# Temperature_sensing_and_heater_power.net
KiCad netlist of a schematic drawn in Altium Designer
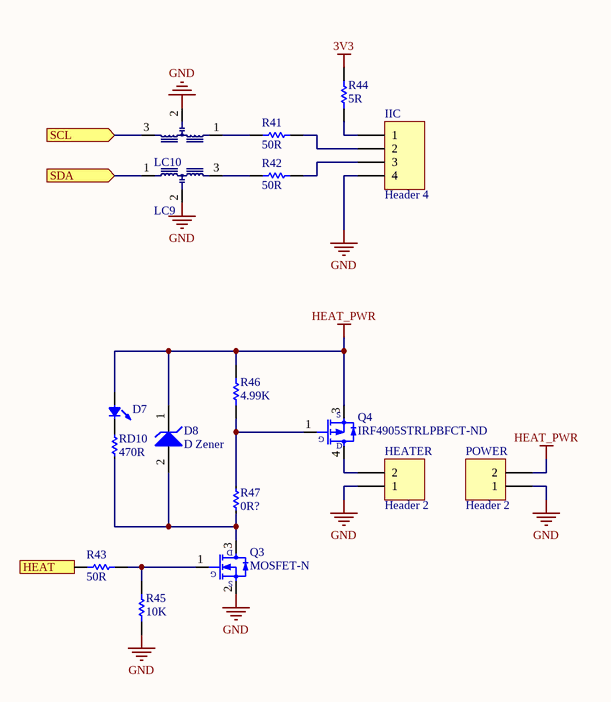
[diagram p0: Temperature sensing and heater power.SchDoc]

(export (version "E")
  (design (tool "Eeschema 10.0.6"))
  (components
    (comp (ref "D7")
      (value "LED0")
      (footprint "T1 LED")
      (description "T 1 3/4 LED")
      (fields (field (name "PUBLISHER") "Altium Limited"))
      (libsource (lib "Miscellaneous Devices") (part "LED0"))
    )
    (comp (ref "D8")
      (value "D Zener")
      (footprint "SOD123/X.85")
      (description "Zener Diode")
      (fields (field (name "PUBLISHER") "Altium Limited"))
      (libsource (lib "Miscellaneous Devices") (part "D Zener"))
    )
    (comp (ref "HEATER")
      (value "Header 2")
      (footprint "Molex Mini-Fit Jr 5569 - 2 Pin, RA")
      (description "Header, 2-Pin")
      (fields (field (name "PUBLISHER") "Altium Limited"))
      (libsource (lib "") (part "Header 2_1"))
    )
    (comp (ref "IIC")
      (value "Header 4")
      (footprint "AMPModu MTE 4 Pin Shrouded Header")
      (description "Header, 4-Pin")
      (fields (field (name "PUBLISHER") "Altium Limited"))
      (libsource (lib "Miscellaneous Connectors") (part "Header 4"))
    )
    (comp (ref "LC9")
      (value "MEM2012F")
      (footprint "MEM2012S LC Filter")
      (description "Signal Line 3-terminal Filters")
      (libsource (lib "Unsorted") (part "MEM2012F - Signal Filter"))
    )
    (comp (ref "LC10")
      (value "MEM2012F")
      (footprint "MEM2012S LC Filter")
      (description "Signal Line 3-terminal Filters")
      (libsource (lib "Unsorted") (part "MEM2012F - Signal Filter"))
    )
    (comp (ref "POWER")
      (value "Header 2")
      (footprint "Molex Mini-Fit Jr 5569 - 2 Pin, RA")
      (description "Header, 2-Pin")
      (fields (field (name "PUBLISHER") "Altium Limited"))
      (libsource (lib "Miscellaneous Connectors") (part "Header 2"))
    )
    (comp (ref "Q3")
      (value "MOSFET-N")
      (footprint "SOT23-3N")
      (description "N-Channel MOSFET")
      (fields (field (name "PUBLISHER") "Altium Limited"))
      (libsource (lib "Miscellaneous Devices") (part "MOSFET-N"))
    )
    (comp (ref "Q4")
      (value "IRF4905STRLPBFCT-ND")
      (footprint "TO254P1520-3_4N")
      (description "P-Channel MOSFET")
      (fields (field (name "PUBLISHER") "Altium Limited"))
      (libsource (lib "Miscellaneous Devices") (part "MOSFET-P"))
    )
    (comp (ref "R41")
      (value "50R")
      (footprint "0603R")
      (description "Semiconductor Resistor")
      (fields (field (name "Comment") "Res Semi") (field (name "PUBLISHER") "Altium Limited"))
      (libsource (lib "Miscellaneous Devices") (part "Res Semi"))
    )
    (comp (ref "R42")
      (value "50R")
      (footprint "0603R")
      (description "Semiconductor Resistor")
      (fields (field (name "Comment") "Res Semi") (field (name "PUBLISHER") "Altium Limited"))
      (libsource (lib "Miscellaneous Devices") (part "Res Semi"))
    )
    (comp (ref "R43")
      (value "50R")
      (footprint "0603R")
      (description "Semiconductor Resistor")
      (fields (field (name "Comment") "Res Semi") (field (name "PUBLISHER") "Altium Limited"))
      (libsource (lib "Miscellaneous Devices") (part "Res Semi"))
    )
    (comp (ref "R44")
      (value "5R")
      (footprint "1206R")
      (description "Semiconductor Resistor")
      (fields (field (name "Comment") "Res Semi") (field (name "PUBLISHER") "Altium Limited"))
      (libsource (lib "Miscellaneous Devices") (part "Res Semi"))
    )
    (comp (ref "R45")
      (value "10K")
      (footprint "0603R")
      (description "Semiconductor Resistor")
      (fields (field (name "Comment") "Res Semi") (field (name "PUBLISHER") "Altium Limited"))
      (libsource (lib "Miscellaneous Devices") (part "Res Semi"))
    )
    (comp (ref "R46")
      (value "4.99K")
      (footprint "1206R")
      (description "Semiconductor Resistor")
      (fields (field (name "Comment") "Res Semi") (field (name "PUBLISHER") "Altium Limited"))
      (libsource (lib "Miscellaneous Devices") (part "Res Semi"))
    )
    (comp (ref "R47")
      (value "0R?")
      (footprint "0603R")
      (description "Semiconductor Resistor")
      (fields (field (name "Comment") "Res Semi Small") (field (name "PUBLISHER") "Altium Limited"))
      (libsource (lib "Miscellaneous Devices") (part "Res Semi Small"))
    )
    (comp (ref "RD10")
      (value "470R")
      (footprint "0603R")
      (description "Semiconductor Resistor")
      (fields (field (name "Comment") "Res Semi Small") (field (name "PUBLISHER") "Altium Limited"))
      (libsource (lib "Miscellaneous Devices") (part "Res Semi Small"))
    )
  )
  (nets
    (net (code "1") (name "/HEAT") (class "Default")
      (node (ref "R43") (pin "1") (pinfunction "1_1") (pintype "passive"))
    )
    (net (code "2") (name "/SCL") (class "Default")
      (node (ref "LC10") (pin "3") (pinfunction "3_3") (pintype "passive"))
    )
    (net (code "3") (name "/SDA") (class "Default")
      (node (ref "LC9") (pin "1") (pinfunction "1_1") (pintype "passive"))
    )
    (net (code "4") (name "3V3") (class "Default")
      (node (ref "R44") (pin "2") (pinfunction "2_2") (pintype "passive"))
    )
    (net (code "5") (name "GND") (class "Default")
      (node (ref "HEATER") (pin "1") (pinfunction "1_1") (pintype "passive"))
      (node (ref "IIC") (pin "4") (pinfunction "4_4") (pintype "passive"))
      (node (ref "LC10") (pin "2") (pinfunction "2_2") (pintype "passive"))
      (node (ref "LC9") (pin "2") (pinfunction "2_2") (pintype "passive"))
      (node (ref "POWER") (pin "1") (pinfunction "1_1") (pintype "passive"))
      (node (ref "Q3") (pin "2") (pinfunction "S_2") (pintype "passive"))
      (node (ref "R45") (pin "1") (pinfunction "1_1") (pintype "passive"))
    )
    (net (code "6") (name "HEAT_PWR") (class "Default")
      (node (ref "D7") (pin "1") (pinfunction "1_1") (pintype "passive"))
      (node (ref "D8") (pin "1") (pinfunction "A_1") (pintype "passive"))
      (node (ref "POWER") (pin "2") (pinfunction "2_2") (pintype "passive"))
      (node (ref "Q4") (pin "3") (pinfunction "D_3") (pintype "passive"))
      (node (ref "R46") (pin "2") (pinfunction "2_2") (pintype "passive"))
    )
    (net (code "7") (name "Net-(D7-Pad2)") (class "Default")
      (node (ref "D7") (pin "2") (pinfunction "2_2") (pintype "passive"))
      (node (ref "RD10") (pin "1") (pinfunction "1_1") (pintype "passive"))
    )
    (net (code "8") (name "Net-(D8-K)") (class "Default")
      (node (ref "D8") (pin "2") (pinfunction "K_2") (pintype "passive"))
      (node (ref "Q3") (pin "3") (pinfunction "D_3") (pintype "passive"))
      (node (ref "R47") (pin "2") (pinfunction "2_2") (pintype "passive"))
      (node (ref "RD10") (pin "2") (pinfunction "2_2") (pintype "passive"))
    )
    (net (code "9") (name "Net-(IIC-Pad1)") (class "Default")
      (node (ref "IIC") (pin "1") (pinfunction "1_1") (pintype "passive"))
      (node (ref "R44") (pin "1") (pinfunction "1_1") (pintype "passive"))
    )
    (net (code "10") (name "Net-(IIC-Pad2)") (class "Default")
      (node (ref "IIC") (pin "2") (pinfunction "2_2") (pintype "passive"))
      (node (ref "R41") (pin "2") (pinfunction "2_2") (pintype "passive"))
    )
    (net (code "11") (name "Net-(IIC-Pad3)") (class "Default")
      (node (ref "IIC") (pin "3") (pinfunction "3_3") (pintype "passive"))
      (node (ref "R42") (pin "2") (pinfunction "2_2") (pintype "passive"))
    )
    (net (code "12") (name "Net-(LC9-Pad3)") (class "Default")
      (node (ref "LC9") (pin "3") (pinfunction "3_3") (pintype "passive"))
      (node (ref "R42") (pin "1") (pinfunction "1_1") (pintype "passive"))
    )
    (net (code "13") (name "Net-(LC10-Pad1)") (class "Default")
      (node (ref "LC10") (pin "1") (pinfunction "1_1") (pintype "passive"))
      (node (ref "R41") (pin "1") (pinfunction "1_1") (pintype "passive"))
    )
    (net (code "14") (name "Net-(Q3-G)") (class "Default")
      (node (ref "Q3") (pin "1") (pinfunction "G_1") (pintype "passive"))
      (node (ref "R43") (pin "2") (pinfunction "2_2") (pintype "passive"))
      (node (ref "R45") (pin "2") (pinfunction "2_2") (pintype "passive"))
    )
    (net (code "15") (name "Net-(Q4-G)") (class "Default")
      (node (ref "Q4") (pin "1") (pinfunction "G_1") (pintype "passive"))
      (node (ref "R46") (pin "1") (pinfunction "1_1") (pintype "passive"))
      (node (ref "R47") (pin "1") (pinfunction "1_1") (pintype "passive"))
    )
    (net (code "16") (name "Net-(Q4-S)") (class "Default")
      (node (ref "HEATER") (pin "2") (pinfunction "2_2") (pintype "passive"))
      (node (ref "Q4") (pin "4") (pinfunction "S_4") (pintype "passive"))
    )
  )
)
